# ChargerDetection.net
KiCad netlist of a schematic drawn in Altium Designer
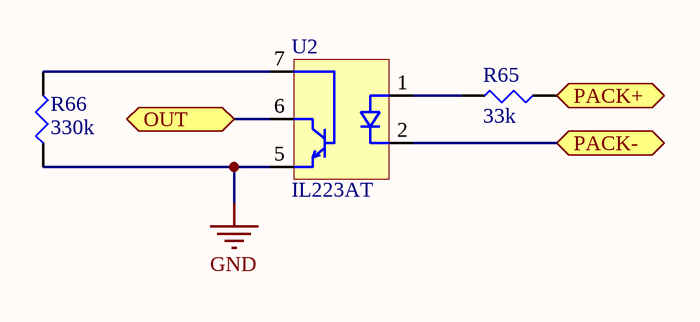
[diagram p0: ChargerDetection.SchDoc]

(export (version "E")
  (design (tool "Eeschema 10.0.6"))
  (components
    (comp (ref "R65")
      (value "33k")
      (footprint "SMD-0603-RES")
      (description "RES SMD 33K OHM 1% 1/10W 0603")
      (fields
        (field (name "PART NUMBER") "ERJ-3EKF3302V")
        (field (name "DIGI-KEY PART NUMBER") "P33.0KHCT-ND")
      )
      (libsource (lib "Panasonic_ERJ_0603") (part "ERJ-3EKF3302V"))
    )
    (comp (ref "R66")
      (value "330k")
      (footprint "SMD-0603-RES")
      (description "RES SMD 330K OHM 1% 1/10W 0603")
      (fields
        (field (name "PART NUMBER") "ERJ-3EKF3303V")
        (field (name "DIGI-KEY PART NUMBER") "P330KHCT-ND")
      )
      (libsource (lib "Panasonic_ERJ_0603") (part "ERJ-3EKF3303V"))
    )
    (comp (ref "U2")
      (value "IL223AT")
      (footprint "SOIC-8")
      (description "Optocoupler")
      (libsource (lib "Components") (part "IL223AT"))
    )
  )
  (nets
    (net (code "1") (name "/OUT") (class "Default")
      (node (ref "U2") (pin "6") (pinfunction "C_6") (pintype "passive"))
    )
    (net (code "2") (name "/PACK+") (class "Default")
      (node (ref "R65") (pin "1") (pinfunction "1_1") (pintype "passive"))
    )
    (net (code "3") (name "/PACK-") (class "Default")
      (node (ref "U2") (pin "2") (pinfunction "K_2") (pintype "passive"))
    )
    (net (code "4") (name "GND") (class "Default")
      (node (ref "R66") (pin "1") (pinfunction "1_1") (pintype "passive"))
      (node (ref "U2") (pin "5") (pinfunction "E_5") (pintype "passive"))
    )
    (net (code "5") (name "Net-(U2-A)") (class "Default")
      (node (ref "R65") (pin "2") (pinfunction "2_2") (pintype "passive"))
      (node (ref "U2") (pin "1") (pinfunction "A_1") (pintype "passive"))
    )
    (net (code "6") (name "Net-(U2-B)") (class "Default")
      (node (ref "R66") (pin "2") (pinfunction "2_2") (pintype "passive"))
      (node (ref "U2") (pin "7") (pinfunction "B_7") (pintype "passive"))
    )
  )
)
